# ControlBoard.net
KiCad netlist of a schematic drawn in EAGLE
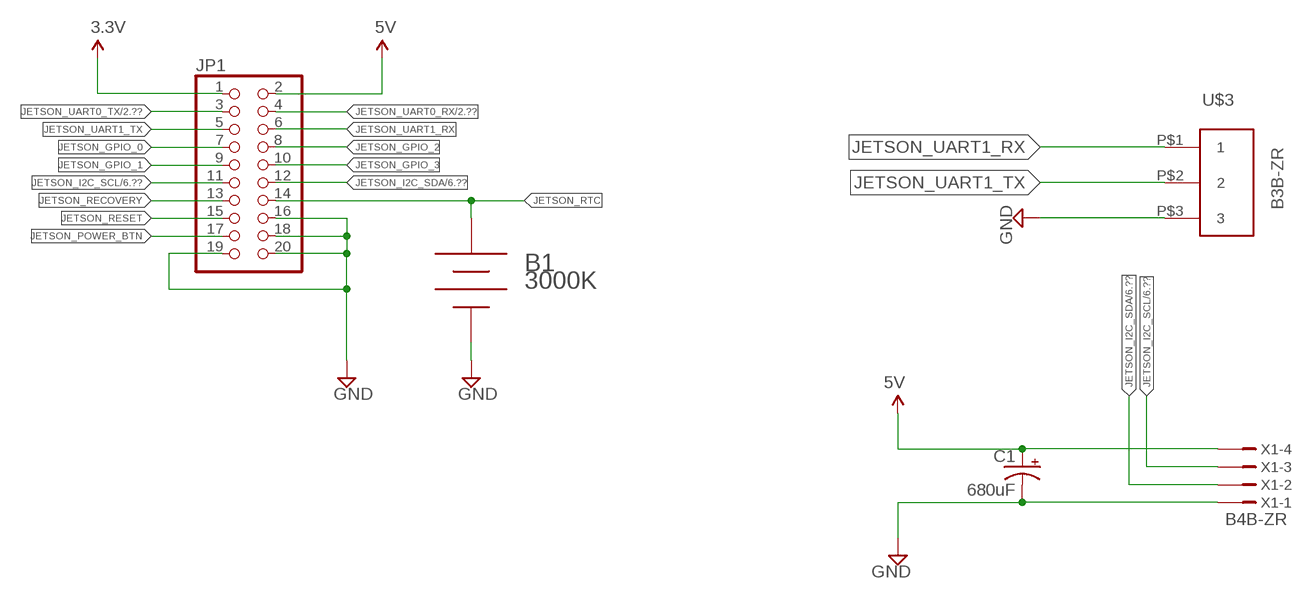
[diagram p0: schematic, sheet 1]
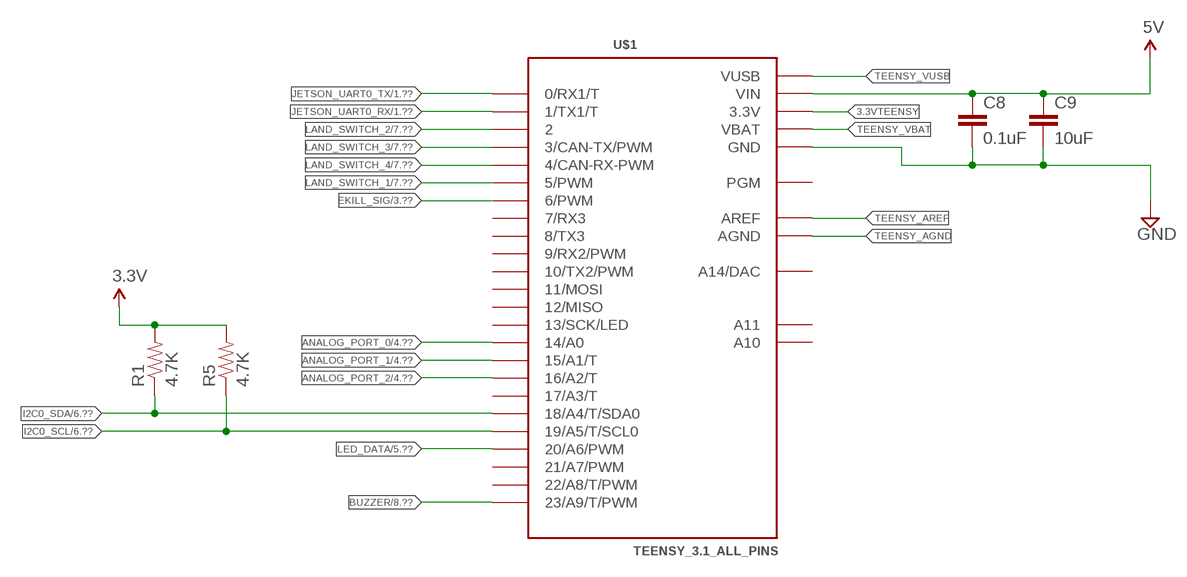
[diagram p1: schematic, sheet 2]
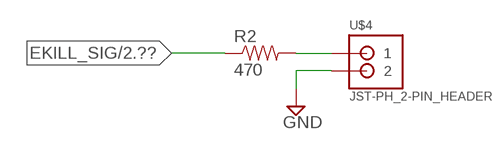
[diagram p2: schematic, sheet 3]
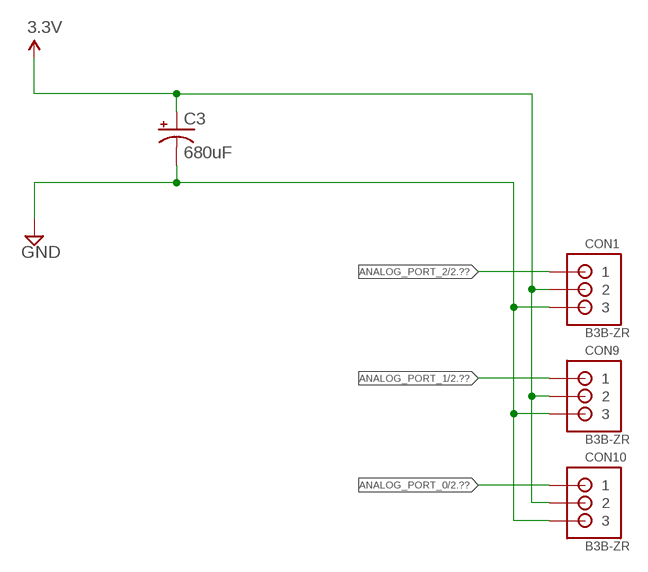
[diagram p3: schematic, sheet 4]
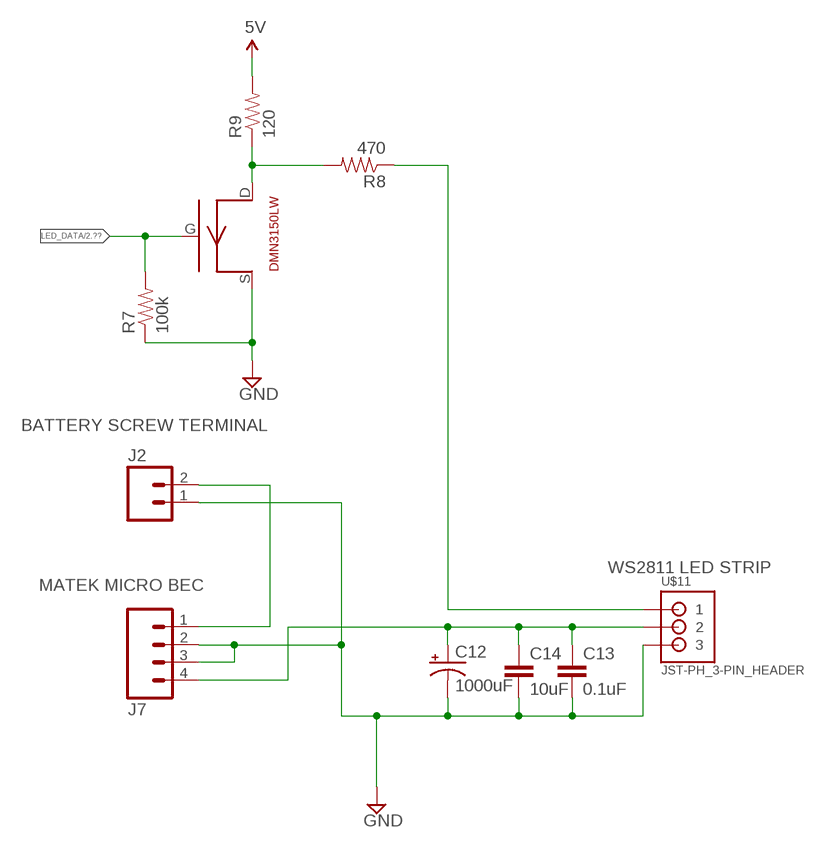
[diagram p4: schematic, sheet 5]
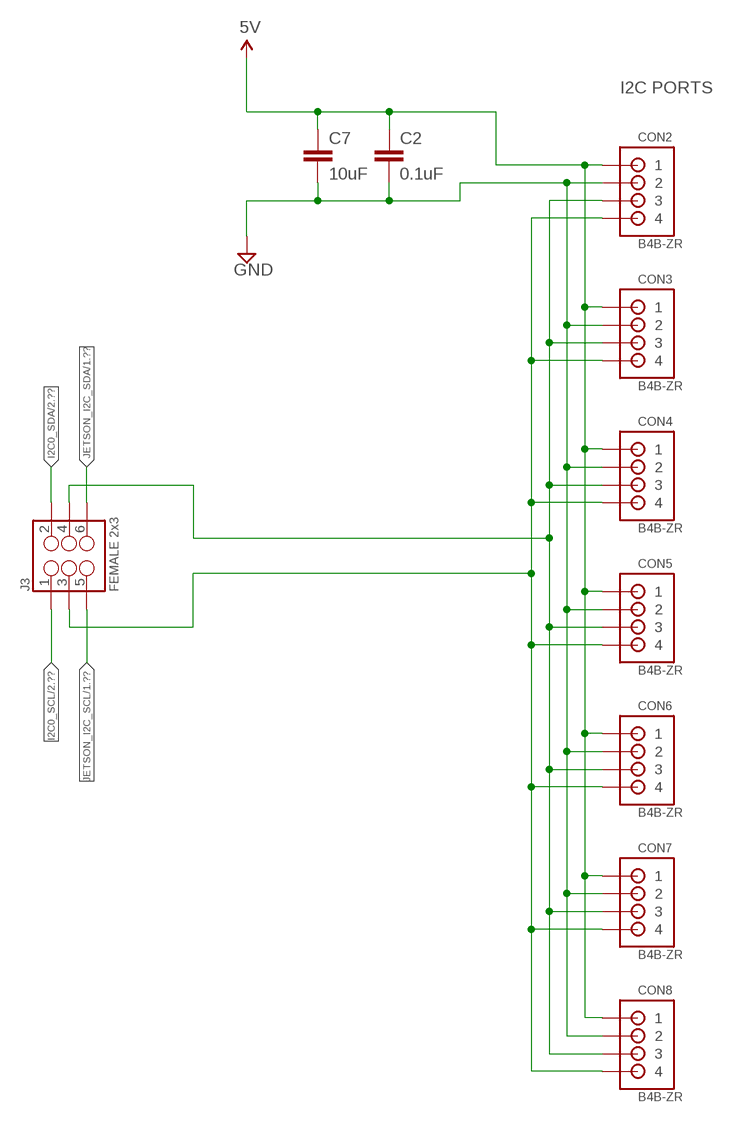
[diagram p5: schematic, sheet 6]
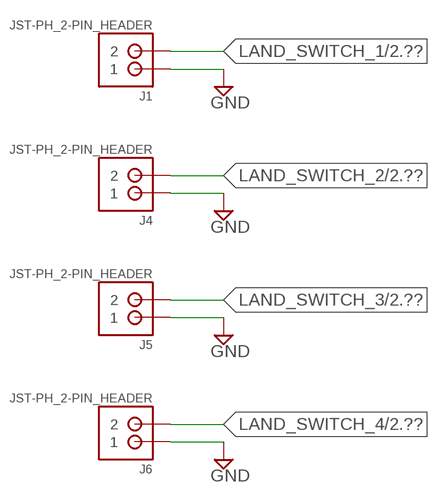
[diagram p6: schematic, sheet 7]
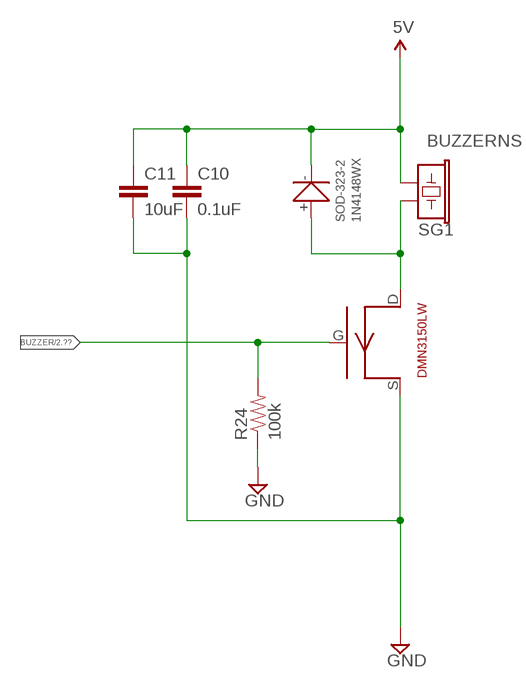
[diagram p7: schematic, sheet 8]

(export (version "E")
  (design (tool "Eeschema 10.0.6"))
  (components
    (comp (ref "C10")
      (value "0.1uF")
      (footprint "eagle-import:0603-CAP")
      (libsource (lib "eagle-import") (part "SparkFun-Passives_CAP0603-CAP"))
    )
    (comp (ref "C11")
      (value "10uF")
      (footprint "eagle-import:0603-CAP")
      (libsource (lib "eagle-import") (part "SparkFun-Passives_CAP0603-CAP"))
    )
    (comp (ref "R24")
      (value "100k")
      (footprint "eagle-import:0603-RES")
      (libsource (lib "eagle-import") (part "RESISTOR0603-RES"))
    )
    (comp (ref "SG1")
      (value "BUZZERNS")
      (footprint "eagle-import:BUZZER-12MM-NS")
      (libsource (lib "eagle-import") (part "BUZZERNS"))
    )
    (comp (ref "U$8")
      (value "1N4148WX_SOD-323-2")
      (footprint "eagle-import:1N4148WX_SOD-323-2")
      (libsource (lib "eagle-import") (part "1N4148WX_SOD-323-2"))
    )
    (comp (ref "U$9")
      (value "DMN3150LW")
      (footprint "eagle-import:DMN3150LW")
      (libsource (lib "eagle-import") (part "DMN3150LW"))
    )
    (comp (ref "R2")
      (value "470")
      (footprint "eagle-import:0603-RES")
      (libsource (lib "eagle-import") (part "RESISTOR0603"))
    )
    (comp (ref "U$4")
      (value "JST-PH_2-PIN_HEADER")
      (footprint "eagle-import:JST_B2B-PH_HEADER")
      (libsource (lib "eagle-import") (part "JST-PH_2-PIN_HEADER"))
    )
    (comp (ref "C8")
      (value "0.1uF")
      (footprint "eagle-import:0603-CAP")
      (libsource (lib "eagle-import") (part "SparkFun-Passives_CAP0603-CAP"))
    )
    (comp (ref "C9")
      (value "10uF")
      (footprint "eagle-import:0603-CAP")
      (libsource (lib "eagle-import") (part "SparkFun-Passives_CAP0603-CAP"))
    )
    (comp (ref "R1")
      (value "4.7K")
      (footprint "eagle-import:0603-RES")
      (libsource (lib "eagle-import") (part "RESISTOR0603"))
    )
    (comp (ref "R5")
      (value "4.7K")
      (footprint "eagle-import:0603-RES")
      (libsource (lib "eagle-import") (part "RESISTOR0603"))
    )
    (comp (ref "U$1")
      (value "TEENSY_3.1_ALL_PINS")
      (footprint "eagle-import:TEENSY3-ALL_PINS")
      (libsource (lib "eagle-import") (part "TEENSY_3.1_ALL_PINS"))
    )
    (comp (ref "C12")
      (value "1000uF")
      (footprint "eagle-import:CPOL-RADIAL-1000UF-25V")
      (libsource (lib "eagle-import") (part "SparkFun-Passives_CAP_POLPTH4"))
    )
    (comp (ref "C13")
      (value "0.1uF")
      (footprint "eagle-import:0603-CAP")
      (libsource (lib "eagle-import") (part "CAP0603-CAP"))
    )
    (comp (ref "C14")
      (value "10uF")
      (footprint "eagle-import:0603-CAP")
      (libsource (lib "eagle-import") (part "CAP0603-CAP"))
    )
    (comp (ref "J2")
      (value "M025MM")
      (footprint "eagle-import:SCREWTERMINAL-5MM-2")
      (libsource (lib "eagle-import") (part "M025MM"))
    )
    (comp (ref "J7")
      (value "M04PTH")
      (footprint "eagle-import:1X04")
      (libsource (lib "eagle-import") (part "M04PTH"))
    )
    (comp (ref "R7")
      (value "100k")
      (footprint "eagle-import:0603-RES")
      (libsource (lib "eagle-import") (part "RESISTOR0603-RES"))
    )
    (comp (ref "R8")
      (value "470")
      (footprint "eagle-import:0603-RES")
      (libsource (lib "eagle-import") (part "RESISTOR0603"))
    )
    (comp (ref "R9")
      (value "120")
      (footprint "eagle-import:0603-RES")
      (libsource (lib "eagle-import") (part "RESISTOR0603"))
    )
    (comp (ref "U$2")
      (value "DMN3150LW")
      (footprint "eagle-import:DMN3150LW")
      (libsource (lib "eagle-import") (part "DMN3150LW"))
    )
    (comp (ref "U$11")
      (value "JST-PH_3-PIN_HEADER")
      (footprint "eagle-import:JST_B3B-PH_HEADER")
      (libsource (lib "eagle-import") (part "JST-PH_3-PIN_HEADER"))
    )
    (comp (ref "B1")
      (value "3000K")
      (footprint "eagle-import:3000K")
      (libsource (lib "eagle-import") (part "3000K"))
    )
    (comp (ref "C1")
      (value "680uF")
      (footprint "eagle-import:CPOL-RADIAL-1000UF-25V")
      (libsource (lib "eagle-import") (part "CAP_POLPTH4"))
    )
    (comp (ref "JP1")
      (value "PINHD-2X10")
      (footprint "eagle-import:2X10")
      (libsource (lib "eagle-import") (part "PINHD-2X10"))
    )
    (comp (ref "U$3")
      (value "B3B-ZR")
      (footprint "eagle-import:3PIN-1.5MM")
      (libsource (lib "eagle-import") (part "B3B-ZR"))
    )
    (comp (ref "X1")
      (value "B4B-ZR")
      (footprint "eagle-import:B4B-ZR")
      (fields (field (name "MF") "FARNELL") (field (name "MPN") "B4B-ZR(LF)(SN)"))
      (libsource (lib "eagle-import") (part "?4B-ZRB"))
    )
    (comp (ref "C2")
      (value "0.1uF")
      (footprint "eagle-import:0603-CAP")
      (libsource (lib "eagle-import") (part "CAP0603-CAP"))
    )
    (comp (ref "C7")
      (value "10uF")
      (footprint "eagle-import:0603-CAP")
      (libsource (lib "eagle-import") (part "CAP0603-CAP"))
    )
    (comp (ref "CON2")
      (value "B4B-ZR")
      (footprint "eagle-import:B4B-ZR")
      (libsource (lib "eagle-import") (part "B4B-ZR"))
    )
    (comp (ref "CON3")
      (value "B4B-ZR")
      (footprint "eagle-import:B4B-ZR")
      (libsource (lib "eagle-import") (part "B4B-ZR"))
    )
    (comp (ref "CON4")
      (value "B4B-ZR")
      (footprint "eagle-import:B4B-ZR")
      (libsource (lib "eagle-import") (part "B4B-ZR"))
    )
    (comp (ref "CON5")
      (value "B4B-ZR")
      (footprint "eagle-import:B4B-ZR")
      (libsource (lib "eagle-import") (part "B4B-ZR"))
    )
    (comp (ref "CON6")
      (value "B4B-ZR")
      (footprint "eagle-import:B4B-ZR")
      (libsource (lib "eagle-import") (part "B4B-ZR"))
    )
    (comp (ref "CON7")
      (value "B4B-ZR")
      (footprint "eagle-import:B4B-ZR")
      (libsource (lib "eagle-import") (part "B4B-ZR"))
    )
    (comp (ref "CON8")
      (value "B4B-ZR")
      (footprint "eagle-import:B4B-ZR")
      (libsource (lib "eagle-import") (part "B4B-ZR"))
    )
    (comp (ref "J3")
      (value "FEMALE 2x3")
      (footprint "eagle-import:2X3")
      (libsource (lib "eagle-import") (part "M03X2FEMALE"))
    )
    (comp (ref "J1")
      (value "JST-PH_2-PIN_HEADER")
      (footprint "eagle-import:JST_B2B-PH_HEADER")
      (libsource (lib "eagle-import") (part "JST-PH_2-PIN_HEADER"))
    )
    (comp (ref "J4")
      (value "JST-PH_2-PIN_HEADER")
      (footprint "eagle-import:JST_B2B-PH_HEADER")
      (libsource (lib "eagle-import") (part "JST-PH_2-PIN_HEADER"))
    )
    (comp (ref "J5")
      (value "JST-PH_2-PIN_HEADER")
      (footprint "eagle-import:JST_B2B-PH_HEADER")
      (libsource (lib "eagle-import") (part "JST-PH_2-PIN_HEADER"))
    )
    (comp (ref "J6")
      (value "JST-PH_2-PIN_HEADER")
      (footprint "eagle-import:JST_B2B-PH_HEADER")
      (libsource (lib "eagle-import") (part "JST-PH_2-PIN_HEADER"))
    )
    (comp (ref "C3")
      (value "680uF")
      (footprint "eagle-import:CPOL-RADIAL-1000UF-25V")
      (libsource (lib "eagle-import") (part "CAP_POLPTH4"))
    )
    (comp (ref "CON1")
      (value "B3B-ZR")
      (footprint "eagle-import:B3B-ZR")
      (libsource (lib "eagle-import") (part "jst_B3B-ZR"))
    )
    (comp (ref "CON9")
      (value "B3B-ZR")
      (footprint "eagle-import:B3B-ZR")
      (libsource (lib "eagle-import") (part "jst_B3B-ZR"))
    )
    (comp (ref "CON10")
      (value "B3B-ZR")
      (footprint "eagle-import:B3B-ZR")
      (libsource (lib "eagle-import") (part "jst_B3B-ZR"))
    )
  )
  (nets
    (net (code "1") (name "3.3V") (class "Default")
      (node (ref "C3") (pin "+") (pinfunction "+_+") (pintype "passive"))
      (node (ref "CON1") (pin "2") (pinfunction "2_2") (pintype "bidirectional"))
      (node (ref "CON10") (pin "2") (pinfunction "2_2") (pintype "bidirectional"))
      (node (ref "CON9") (pin "2") (pinfunction "2_2") (pintype "bidirectional"))
      (node (ref "JP1") (pin "1") (pinfunction "1_1") (pintype "passive"))
      (node (ref "R1") (pin "2") (pinfunction "2_2") (pintype "passive"))
      (node (ref "R5") (pin "2") (pinfunction "2_2") (pintype "passive"))
    )
    (net (code "2") (name "3.3VTEENSY") (class "Default")
      (node (ref "U$1") (pin "3.3V") (pinfunction "3.3V_3.3V") (pintype "power_in"))
      (node (ref "U$1") (pin "3.3V1") (pinfunction "3.3V_3.3V1") (pintype "power_in"))
    )
    (net (code "3") (name "5V") (class "Default")
      (node (ref "C1") (pin "+") (pinfunction "+_+") (pintype "passive"))
      (node (ref "C10") (pin "1") (pinfunction "1_1") (pintype "passive"))
      (node (ref "C11") (pin "1") (pinfunction "1_1") (pintype "passive"))
      (node (ref "C2") (pin "1") (pinfunction "1_1") (pintype "passive"))
      (node (ref "C7") (pin "1") (pinfunction "1_1") (pintype "passive"))
      (node (ref "C8") (pin "1") (pinfunction "1_1") (pintype "passive"))
      (node (ref "C9") (pin "1") (pinfunction "1_1") (pintype "passive"))
      (node (ref "CON2") (pin "1") (pinfunction "1_1") (pintype "bidirectional"))
      (node (ref "CON3") (pin "1") (pinfunction "1_1") (pintype "bidirectional"))
      (node (ref "CON4") (pin "1") (pinfunction "1_1") (pintype "bidirectional"))
      (node (ref "CON5") (pin "1") (pinfunction "1_1") (pintype "bidirectional"))
      (node (ref "CON6") (pin "1") (pinfunction "1_1") (pintype "bidirectional"))
      (node (ref "CON7") (pin "1") (pinfunction "1_1") (pintype "bidirectional"))
      (node (ref "CON8") (pin "1") (pinfunction "1_1") (pintype "bidirectional"))
      (node (ref "JP1") (pin "2") (pinfunction "2_2") (pintype "passive"))
      (node (ref "R9") (pin "2") (pinfunction "2_2") (pintype "passive"))
      (node (ref "SG1") (pin "+") (pinfunction "1_+") (pintype "passive"))
      (node (ref "U$1") (pin "VIN") (pinfunction "VIN_VIN") (pintype "power_in"))
      (node (ref "U$8") (pin "-") (pinfunction "-_-") (pintype "bidirectional"))
      (node (ref "X1") (pin "4") (pinfunction "1_4") (pintype "passive"))
    )
    (net (code "4") (name "ANALOG_PORT_0") (class "Default")
      (node (ref "CON10") (pin "1") (pinfunction "1_1") (pintype "bidirectional"))
      (node (ref "U$1") (pin "14/A0") (pinfunction "14/A0_14/A0") (pintype "bidirectional"))
    )
    (net (code "5") (name "ANALOG_PORT_1") (class "Default")
      (node (ref "CON9") (pin "1") (pinfunction "1_1") (pintype "bidirectional"))
      (node (ref "U$1") (pin "15/A1") (pinfunction "15/A1/T_15/A1") (pintype "bidirectional"))
    )
    (net (code "6") (name "ANALOG_PORT_2") (class "Default")
      (node (ref "CON1") (pin "1") (pinfunction "1_1") (pintype "bidirectional"))
      (node (ref "U$1") (pin "16/A2") (pinfunction "16/A2/T_16/A2") (pintype "bidirectional"))
    )
    (net (code "7") (name "BUZZER") (class "Default")
      (node (ref "R24") (pin "2") (pinfunction "2_2") (pintype "passive"))
      (node (ref "U$1") (pin "23/A9") (pinfunction "23/A9/T/PWM_23/A9") (pintype "bidirectional"))
      (node (ref "U$9") (pin "G") (pinfunction "G_G") (pintype "bidirectional"))
    )
    (net (code "8") (name "EKILL_SIG") (class "Default")
      (node (ref "R2") (pin "1") (pinfunction "1_1") (pintype "passive"))
      (node (ref "U$1") (pin "6") (pinfunction "6/PWM_6") (pintype "bidirectional"))
    )
    (net (code "9") (name "GND") (class "Default")
      (node (ref "B1") (pin "-") (pinfunction "-_-") (pintype "power_in"))
      (node (ref "C1") (pin "-") (pinfunction "-_-") (pintype "passive"))
      (node (ref "C10") (pin "2") (pinfunction "2_2") (pintype "passive"))
      (node (ref "C11") (pin "2") (pinfunction "2_2") (pintype "passive"))
      (node (ref "C12") (pin "2") (pinfunction "-_2") (pintype "passive"))
      (node (ref "C13") (pin "2") (pinfunction "2_2") (pintype "passive"))
      (node (ref "C14") (pin "2") (pinfunction "2_2") (pintype "passive"))
      (node (ref "C2") (pin "2") (pinfunction "2_2") (pintype "passive"))
      (node (ref "C3") (pin "-") (pinfunction "-_-") (pintype "passive"))
      (node (ref "C7") (pin "2") (pinfunction "2_2") (pintype "passive"))
      (node (ref "C8") (pin "2") (pinfunction "2_2") (pintype "passive"))
      (node (ref "C9") (pin "2") (pinfunction "2_2") (pintype "passive"))
      (node (ref "CON1") (pin "3") (pinfunction "3_3") (pintype "bidirectional"))
      (node (ref "CON10") (pin "3") (pinfunction "3_3") (pintype "bidirectional"))
      (node (ref "CON2") (pin "2") (pinfunction "2_2") (pintype "bidirectional"))
      (node (ref "CON3") (pin "2") (pinfunction "2_2") (pintype "bidirectional"))
      (node (ref "CON4") (pin "2") (pinfunction "2_2") (pintype "bidirectional"))
      (node (ref "CON5") (pin "2") (pinfunction "2_2") (pintype "bidirectional"))
      (node (ref "CON6") (pin "2") (pinfunction "2_2") (pintype "bidirectional"))
      (node (ref "CON7") (pin "2") (pinfunction "2_2") (pintype "bidirectional"))
      (node (ref "CON8") (pin "2") (pinfunction "2_2") (pintype "bidirectional"))
      (node (ref "CON9") (pin "3") (pinfunction "3_3") (pintype "bidirectional"))
      (node (ref "J1") (pin "P1") (pinfunction "1_P1") (pintype "bidirectional"))
      (node (ref "J2") (pin "1") (pinfunction "1_1") (pintype "passive"))
      (node (ref "J4") (pin "P1") (pinfunction "1_P1") (pintype "bidirectional"))
      (node (ref "J5") (pin "P1") (pinfunction "1_P1") (pintype "bidirectional"))
      (node (ref "J6") (pin "P1") (pinfunction "1_P1") (pintype "bidirectional"))
      (node (ref "J7") (pin "2") (pinfunction "2_2") (pintype "passive"))
      (node (ref "J7") (pin "3") (pinfunction "3_3") (pintype "passive"))
      (node (ref "JP1") (pin "16") (pinfunction "16_16") (pintype "passive"))
      (node (ref "JP1") (pin "18") (pinfunction "18_18") (pintype "passive"))
      (node (ref "JP1") (pin "19") (pinfunction "19_19") (pintype "passive"))
      (node (ref "JP1") (pin "20") (pinfunction "20_20") (pintype "passive"))
      (node (ref "R24") (pin "1") (pinfunction "1_1") (pintype "passive"))
      (node (ref "R7") (pin "1") (pinfunction "1_1") (pintype "passive"))
      (node (ref "U$1") (pin "GND") (pinfunction "GND_GND") (pintype "power_in"))
      (node (ref "U$1") (pin "GND1") (pinfunction "GND_GND1") (pintype "power_in"))
      (node (ref "U$11") (pin "P3") (pinfunction "3_P3") (pintype "bidirectional"))
      (node (ref "U$2") (pin "S") (pinfunction "S_S") (pintype "bidirectional"))
      (node (ref "U$3") (pin "P$3") (pinfunction "3_P$3") (pintype "bidirectional"))
      (node (ref "U$4") (pin "P2") (pinfunction "2_P2") (pintype "bidirectional"))
      (node (ref "U$9") (pin "S") (pinfunction "S_S") (pintype "bidirectional"))
      (node (ref "X1") (pin "1") (pinfunction "1_1") (pintype "passive"))
    )
    (net (code "10") (name "I2C0_SCL") (class "Default")
      (node (ref "J3") (pin "1") (pinfunction "1_1") (pintype "bidirectional"))
      (node (ref "R5") (pin "1") (pinfunction "1_1") (pintype "passive"))
      (node (ref "U$1") (pin "19/A5") (pinfunction "19/A5/T/SCL0_19/A5") (pintype "bidirectional"))
    )
    (net (code "11") (name "I2C0_SDA") (class "Default")
      (node (ref "J3") (pin "2") (pinfunction "2_2") (pintype "bidirectional"))
      (node (ref "R1") (pin "1") (pinfunction "1_1") (pintype "passive"))
      (node (ref "U$1") (pin "18/A4") (pinfunction "18/A4/T/SDA0_18/A4") (pintype "bidirectional"))
    )
    (net (code "12") (name "JETSON_GPIO_0") (class "Default")
      (node (ref "JP1") (pin "7") (pinfunction "7_7") (pintype "passive"))
    )
    (net (code "13") (name "JETSON_GPIO_1") (class "Default")
      (node (ref "JP1") (pin "9") (pinfunction "9_9") (pintype "passive"))
    )
    (net (code "14") (name "JETSON_GPIO_2") (class "Default")
      (node (ref "JP1") (pin "8") (pinfunction "8_8") (pintype "passive"))
    )
    (net (code "15") (name "JETSON_GPIO_3") (class "Default")
      (node (ref "JP1") (pin "10") (pinfunction "10_10") (pintype "passive"))
    )
    (net (code "16") (name "JETSON_I2C_SCL") (class "Default")
      (node (ref "J3") (pin "5") (pinfunction "5_5") (pintype "bidirectional"))
      (node (ref "JP1") (pin "11") (pinfunction "11_11") (pintype "passive"))
      (node (ref "X1") (pin "3") (pinfunction "1_3") (pintype "passive"))
    )
    (net (code "17") (name "JETSON_I2C_SDA") (class "Default")
      (node (ref "J3") (pin "6") (pinfunction "6_6") (pintype "bidirectional"))
      (node (ref "JP1") (pin "12") (pinfunction "12_12") (pintype "passive"))
      (node (ref "X1") (pin "2") (pinfunction "1_2") (pintype "passive"))
    )
    (net (code "18") (name "JETSON_POWER_BTN") (class "Default")
      (node (ref "JP1") (pin "17") (pinfunction "17_17") (pintype "passive"))
    )
    (net (code "19") (name "JETSON_RECOVERY") (class "Default")
      (node (ref "JP1") (pin "13") (pinfunction "13_13") (pintype "passive"))
    )
    (net (code "20") (name "JETSON_RESET") (class "Default")
      (node (ref "JP1") (pin "15") (pinfunction "15_15") (pintype "passive"))
    )
    (net (code "21") (name "JETSON_RTC") (class "Default")
      (node (ref "B1") (pin "+") (pinfunction "+_+") (pintype "power_in"))
      (node (ref "JP1") (pin "14") (pinfunction "14_14") (pintype "passive"))
    )
    (net (code "22") (name "JETSON_UART0_RX") (class "Default")
      (node (ref "JP1") (pin "4") (pinfunction "4_4") (pintype "passive"))
      (node (ref "U$1") (pin "1") (pinfunction "1/TX1/T_1") (pintype "bidirectional"))
    )
    (net (code "23") (name "JETSON_UART0_TX") (class "Default")
      (node (ref "JP1") (pin "3") (pinfunction "3_3") (pintype "passive"))
      (node (ref "U$1") (pin "0") (pinfunction "0/RX1/T_0") (pintype "bidirectional"))
    )
    (net (code "24") (name "JETSON_UART1_RX") (class "Default")
      (node (ref "JP1") (pin "6") (pinfunction "6_6") (pintype "passive"))
      (node (ref "U$3") (pin "P$1") (pinfunction "1_P$1") (pintype "bidirectional"))
    )
    (net (code "25") (name "JETSON_UART1_TX") (class "Default")
      (node (ref "JP1") (pin "5") (pinfunction "5_5") (pintype "passive"))
      (node (ref "U$3") (pin "P$2") (pinfunction "2_P$2") (pintype "bidirectional"))
    )
    (net (code "26") (name "LAND_SWITCH_1") (class "Default")
      (node (ref "J1") (pin "P2") (pinfunction "2_P2") (pintype "bidirectional"))
      (node (ref "U$1") (pin "5") (pinfunction "5/PWM_5") (pintype "bidirectional"))
    )
    (net (code "27") (name "LAND_SWITCH_2") (class "Default")
      (node (ref "J4") (pin "P2") (pinfunction "2_P2") (pintype "bidirectional"))
      (node (ref "U$1") (pin "2") (pinfunction "2_2") (pintype "bidirectional"))
    )
    (net (code "28") (name "LAND_SWITCH_3") (class "Default")
      (node (ref "J5") (pin "P2") (pinfunction "2_P2") (pintype "bidirectional"))
      (node (ref "U$1") (pin "3") (pinfunction "3/CAN-TX/PWM_3") (pintype "bidirectional"))
    )
    (net (code "29") (name "LAND_SWITCH_4") (class "Default")
      (node (ref "J6") (pin "P2") (pinfunction "2_P2") (pintype "bidirectional"))
      (node (ref "U$1") (pin "4") (pinfunction "4/CAN-RX-PWM_4") (pintype "bidirectional"))
    )
    (net (code "30") (name "LED_DATA") (class "Default")
      (node (ref "R7") (pin "2") (pinfunction "2_2") (pintype "passive"))
      (node (ref "U$1") (pin "20/A6") (pinfunction "20/A6/PWM_20/A6") (pintype "bidirectional"))
      (node (ref "U$2") (pin "G") (pinfunction "G_G") (pintype "bidirectional"))
    )
    (net (code "31") (name "Net-(C12-+)") (class "Default")
      (node (ref "C12") (pin "1") (pinfunction "+_1") (pintype "passive"))
      (node (ref "C13") (pin "1") (pinfunction "1_1") (pintype "passive"))
      (node (ref "C14") (pin "1") (pinfunction "1_1") (pintype "passive"))
      (node (ref "J7") (pin "4") (pinfunction "4_4") (pintype "passive"))
      (node (ref "U$11") (pin "P2") (pinfunction "2_P2") (pintype "bidirectional"))
    )
    (net (code "32") (name "Net-(CON2-Pad3)") (class "Default")
      (node (ref "CON2") (pin "3") (pinfunction "3_3") (pintype "bidirectional"))
      (node (ref "CON3") (pin "3") (pinfunction "3_3") (pintype "bidirectional"))
      (node (ref "CON4") (pin "3") (pinfunction "3_3") (pintype "bidirectional"))
      (node (ref "CON5") (pin "3") (pinfunction "3_3") (pintype "bidirectional"))
      (node (ref "CON6") (pin "3") (pinfunction "3_3") (pintype "bidirectional"))
      (node (ref "CON7") (pin "3") (pinfunction "3_3") (pintype "bidirectional"))
      (node (ref "CON8") (pin "3") (pinfunction "3_3") (pintype "bidirectional"))
      (node (ref "J3") (pin "4") (pinfunction "4_4") (pintype "bidirectional"))
    )
    (net (code "33") (name "Net-(CON2-Pad4)") (class "Default")
      (node (ref "CON2") (pin "4") (pinfunction "4_4") (pintype "bidirectional"))
      (node (ref "CON3") (pin "4") (pinfunction "4_4") (pintype "bidirectional"))
      (node (ref "CON4") (pin "4") (pinfunction "4_4") (pintype "bidirectional"))
      (node (ref "CON5") (pin "4") (pinfunction "4_4") (pintype "bidirectional"))
      (node (ref "CON6") (pin "4") (pinfunction "4_4") (pintype "bidirectional"))
      (node (ref "CON7") (pin "4") (pinfunction "4_4") (pintype "bidirectional"))
      (node (ref "CON8") (pin "4") (pinfunction "4_4") (pintype "bidirectional"))
      (node (ref "J3") (pin "3") (pinfunction "3_3") (pintype "bidirectional"))
    )
    (net (code "34") (name "Net-(J2-Pad2)") (class "Default")
      (node (ref "J2") (pin "2") (pinfunction "2_2") (pintype "passive"))
      (node (ref "J7") (pin "1") (pinfunction "1_1") (pintype "passive"))
    )
    (net (code "35") (name "Net-(R8-Pad2)") (class "Default")
      (node (ref "R8") (pin "2") (pinfunction "2_2") (pintype "passive"))
      (node (ref "R9") (pin "1") (pinfunction "1_1") (pintype "passive"))
      (node (ref "U$2") (pin "D") (pinfunction "D_D") (pintype "bidirectional"))
    )
    (net (code "36") (name "Net-(SG1-2)") (class "Default")
      (node (ref "SG1") (pin "-") (pinfunction "2_-") (pintype "passive"))
      (node (ref "U$8") (pin "+") (pinfunction "+_+") (pintype "bidirectional"))
      (node (ref "U$9") (pin "D") (pinfunction "D_D") (pintype "bidirectional"))
    )
    (net (code "37") (name "Net-(U$4-1)") (class "Default")
      (node (ref "R2") (pin "2") (pinfunction "2_2") (pintype "passive"))
      (node (ref "U$4") (pin "P1") (pinfunction "1_P1") (pintype "bidirectional"))
    )
    (net (code "38") (name "Net-(U$11-1)") (class "Default")
      (node (ref "R8") (pin "1") (pinfunction "1_1") (pintype "passive"))
      (node (ref "U$11") (pin "P1") (pinfunction "1_P1") (pintype "bidirectional"))
    )
    (net (code "39") (name "TEENSY_AGND") (class "Default")
      (node (ref "U$1") (pin "AGND") (pinfunction "AGND_AGND") (pintype "power_in"))
    )
    (net (code "40") (name "TEENSY_AREF") (class "Default")
      (node (ref "U$1") (pin "AREF") (pinfunction "AREF_AREF") (pintype "power_in"))
    )
    (net (code "41") (name "TEENSY_VBAT") (class "Default")
      (node (ref "U$1") (pin "VBAT") (pinfunction "VBAT_VBAT") (pintype "power_in"))
    )
    (net (code "42") (name "TEENSY_VUSB") (class "Default")
      (node (ref "U$1") (pin "VUSB") (pinfunction "VUSB_VUSB") (pintype "power_in"))
    )
    (net (code "43") (name "unconnected-(U$1-7{slash}RX3-Pad7)") (class "Default")
      (node (ref "U$1") (pin "7") (pinfunction "7/RX3_7") (pintype "bidirectional"))
    )
    (net (code "44") (name "unconnected-(U$1-8{slash}TX3-Pad8)") (class "Default")
      (node (ref "U$1") (pin "8") (pinfunction "8/TX3_8") (pintype "bidirectional"))
    )
    (net (code "45") (name "unconnected-(U$1-9{slash}RX2{slash}PWM-Pad9)") (class "Default")
      (node (ref "U$1") (pin "9") (pinfunction "9/RX2/PWM_9") (pintype "bidirectional"))
    )
    (net (code "46") (name "unconnected-(U$1-10{slash}TX2{slash}PWM-Pad10)") (class "Default")
      (node (ref "U$1") (pin "10") (pinfunction "10/TX2/PWM_10") (pintype "bidirectional"))
    )
    (net (code "47") (name "unconnected-(U$1-11{slash}MOSI-Pad11)") (class "Default")
      (node (ref "U$1") (pin "11") (pinfunction "11/MOSI_11") (pintype "bidirectional"))
    )
    (net (code "48") (name "unconnected-(U$1-12{slash}MISO-Pad12)") (class "Default")
      (node (ref "U$1") (pin "12") (pinfunction "12/MISO_12") (pintype "bidirectional"))
    )
    (net (code "49") (name "unconnected-(U$1-13{slash}SCK{slash}LED-Pad13)") (class "Default")
      (node (ref "U$1") (pin "13") (pinfunction "13/SCK/LED_13") (pintype "bidirectional"))
    )
    (net (code "50") (name "unconnected-(U$1-17{slash}A3{slash}T-Pad17{slash}A3)") (class "Default")
      (node (ref "U$1") (pin "17/A3") (pinfunction "17/A3/T_17/A3") (pintype "bidirectional"))
    )
    (net (code "51") (name "unconnected-(U$1-21{slash}A7{slash}PWM-Pad21{slash}A7)") (class "Default")
      (node (ref "U$1") (pin "21/A7") (pinfunction "21/A7/PWM_21/A7") (pintype "bidirectional"))
    )
    (net (code "52") (name "unconnected-(U$1-22{slash}A8{slash}T{slash}PWM-Pad22{slash}A8)") (class "Default")
      (node (ref "U$1") (pin "22/A8") (pinfunction "22/A8/T/PWM_22/A8") (pintype "bidirectional"))
    )
    (net (code "53") (name "unconnected-(U$1-A14{slash}DAC-PadRESET{slash}DAC)") (class "Default")
      (node (ref "U$1") (pin "RESET/DAC") (pinfunction "A14/DAC_RESET/DAC") (pintype "bidirectional"))
    )
    (net (code "54") (name "unconnected-(U$1-PadA10)") (class "Default")
      (node (ref "U$1") (pin "A10") (pinfunction "A10_A10") (pintype "bidirectional"))
    )
    (net (code "55") (name "unconnected-(U$1-PadA11)") (class "Default")
      (node (ref "U$1") (pin "A11") (pinfunction "A11_A11") (pintype "bidirectional"))
    )
    (net (code "56") (name "unconnected-(U$1-PadPGM)") (class "Default")
      (node (ref "U$1") (pin "PGM") (pinfunction "PGM_PGM") (pintype "bidirectional"))
    )
  )
)
